# GPS.net
KiCad netlist of a schematic drawn in Altium Designer
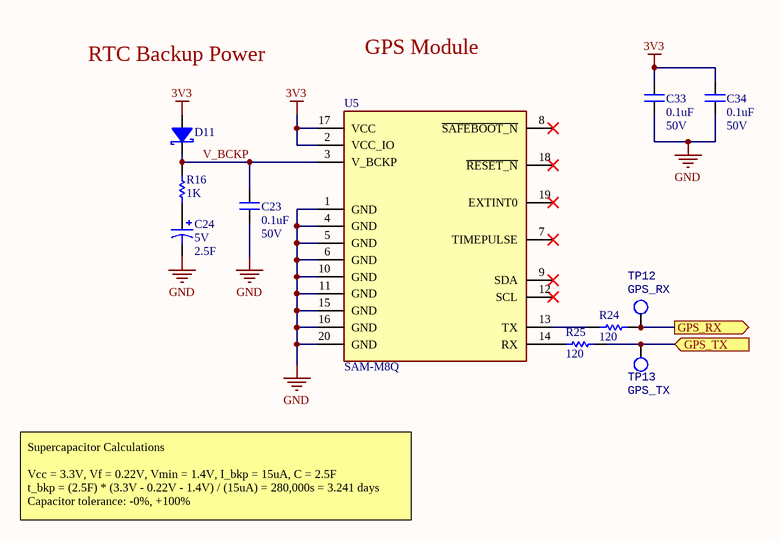
[diagram p0: GPS.SchDoc]

(export (version "E")
  (design (tool "Eeschema 10.0.6"))
  (components
    (comp (ref "C23")
      (value "0.1uF")
      (footprint "CAPC2012X140N")
      (description "CAP CER 0.1UF 50V X7R 0805")
      (fields
        (field (name "TOLERANCE") "10%")
        (field (name "VOLTAGE RATING") "50V")
        (field (name "Comment") "CAP_0.1uF_50V_0805")
      )
      (libsource (lib "UWRT_Schematic_Library_2020") (part "CAP_0.1uF_50V_0805"))
    )
    (comp (ref "C24")
      (value "CAP_2.5F_5V")
      (footprint "UWRT_Footprint_Library_2020:SCMS22C255PRBA0")
      (description "CAP 2.5F 5V")
      (fields
        (field (name "TOLERANCE") "0%, +100%")
        (field (name "VOLTAGE RATING") "5V")
        (field (name "CAPACITANCE") "2.5F")
      )
      (libsource (lib "UWRT_Schematic_Library_2020") (part "CAP_2.5F_5V"))
    )
    (comp (ref "C33")
      (value "0.1uF")
      (footprint "CAPC2012X140N")
      (description "CAP CER 0.1UF 50V X7R 0805")
      (fields
        (field (name "TOLERANCE") "10%")
        (field (name "VOLTAGE RATING") "50V")
        (field (name "Comment") "CAP_0.1uF_50V_0805")
      )
      (libsource (lib "UWRT_Schematic_Library_2020") (part "CAP_0.1uF_50V_0805"))
    )
    (comp (ref "C34")
      (value "0.1uF")
      (footprint "CAPC2012X140N")
      (description "CAP CER 0.1UF 50V X7R 0805")
      (fields
        (field (name "TOLERANCE") "10%")
        (field (name "VOLTAGE RATING") "50V")
        (field (name "Comment") "CAP_0.1uF_50V_0805")
      )
      (libsource (lib "UWRT_Schematic_Library_2020") (part "CAP_0.1uF_50V_0805"))
    )
    (comp (ref "D11")
      (value "DIO_SCHOTTKY_30V_800mA")
      (footprint "DIO_CUS520,H3F")
      (description "DIODE SCHOTTKY 30V 800MA USC")
      (libsource (lib "UWRT_Schematic_Library_2020") (part "DIO_SCHOTTKY_30V_800mA"))
    )
    (comp (ref "R16")
      (value "1K")
      (footprint "RESC0603(1608)_N")
      (description "RES SMD 1K OHM 5% 1/10W 0603")
      (fields (field (name "TOLERANCE") "5%") (field (name "Comment") "RES_1K_0603"))
      (libsource (lib "UWRT_Schematic_Library_2020") (part "RES_1K_0603"))
    )
    (comp (ref "R24")
      (value "120")
      (footprint "RESC0603(1608)_N")
      (description "RES SMD 120 OHM 5% 1/10W 0603")
      (fields (field (name "TOLERANCE") "5%") (field (name "Comment") "RES_120R_0603"))
      (libsource (lib "UWRT_Schematic_Library_2020") (part "RES_120R_0603"))
    )
    (comp (ref "R25")
      (value "120")
      (footprint "RESC0603(1608)_N")
      (description "RES SMD 120 OHM 5% 1/10W 0603")
      (fields (field (name "TOLERANCE") "5%") (field (name "Comment") "RES_120R_0603"))
      (libsource (lib "UWRT_Schematic_Library_2020") (part "RES_120R_0603"))
    )
    (comp (ref "TP12")
      (value "GPS_RX")
      (footprint "TESTPOINT_LOOP")
      (description "Loop testpoint through-hole pad")
      (libsource (lib "UWRT_Schematic_Library_2020") (part "TESTPOINT_LOOP"))
    )
    (comp (ref "TP13")
      (value "GPS_TX")
      (footprint "TESTPOINT_LOOP")
      (description "Loop testpoint through-hole pad")
      (libsource (lib "UWRT_Schematic_Library_2020") (part "TESTPOINT_LOOP"))
    )
    (comp (ref "U5")
      (value "SAM-M8Q")
      (footprint "UWRT_Footprint_Library_2020:XCVR_SAM-M8Q")
      (description "Rf Rx Galileo 1.575GHZ/1.602GHZ")
      (libsource (lib "UWRT_Schematic_Library_2020") (part "SAM-M8Q"))
    )
  )
  (nets
    (net (code "1") (name "/GPS_RX") (class "Default")
      (node (ref "R24") (pin "2") (pinfunction "2_2") (pintype "passive"))
      (node (ref "TP12") (pin "1") (pintype "passive"))
    )
    (net (code "2") (name "/GPS_TX") (class "Default")
      (node (ref "R25") (pin "2") (pinfunction "2_2") (pintype "passive"))
      (node (ref "TP13") (pin "1") (pintype "passive"))
    )
    (net (code "3") (name "/V_BCKP") (class "Default")
      (node (ref "C23") (pin "2") (pinfunction "2_2") (pintype "passive"))
      (node (ref "D11") (pin "2") (pinfunction "Cathode_2") (pintype "passive"))
      (node (ref "R16") (pin "1") (pinfunction "1_1") (pintype "passive"))
      (node (ref "U5") (pin "3") (pinfunction "V_BCKP_3") (pintype "power_in"))
    )
    (net (code "4") (name "3V3") (class "Default")
      (node (ref "C33") (pin "2") (pinfunction "2_2") (pintype "passive"))
      (node (ref "C34") (pin "2") (pinfunction "2_2") (pintype "passive"))
      (node (ref "D11") (pin "1") (pinfunction "Anode_1") (pintype "passive"))
      (node (ref "U5") (pin "17") (pinfunction "VCC_17") (pintype "power_in"))
      (node (ref "U5") (pin "2") (pinfunction "VCC_IO_2") (pintype "power_in"))
    )
    (net (code "5") (name "GND") (class "Default")
      (node (ref "C23") (pin "1") (pinfunction "1_1") (pintype "passive"))
      (node (ref "C24") (pin "2") (pinfunction "2_2") (pintype "passive"))
      (node (ref "C33") (pin "1") (pinfunction "1_1") (pintype "passive"))
      (node (ref "C34") (pin "1") (pinfunction "1_1") (pintype "passive"))
      (node (ref "U5") (pin "1") (pinfunction "GND_1") (pintype "power_in"))
      (node (ref "U5") (pin "10") (pinfunction "GND_10") (pintype "power_in"))
      (node (ref "U5") (pin "11") (pinfunction "GND_11") (pintype "power_in"))
      (node (ref "U5") (pin "15") (pinfunction "GND_15") (pintype "power_in"))
      (node (ref "U5") (pin "16") (pinfunction "GND_16") (pintype "power_in"))
      (node (ref "U5") (pin "20") (pinfunction "GND_20") (pintype "power_in"))
      (node (ref "U5") (pin "4") (pinfunction "GND_4") (pintype "power_in"))
      (node (ref "U5") (pin "5") (pinfunction "GND_5") (pintype "power_in"))
      (node (ref "U5") (pin "6") (pinfunction "GND_6") (pintype "power_in"))
    )
    (net (code "6") (name "Net-(C24-Pad1)") (class "Default")
      (node (ref "C24") (pin "1") (pinfunction "1_1") (pintype "passive"))
      (node (ref "R16") (pin "2") (pinfunction "2_2") (pintype "passive"))
    )
    (net (code "7") (name "Net-(U5-RX)") (class "Default")
      (node (ref "R25") (pin "1") (pinfunction "1_1") (pintype "passive"))
      (node (ref "U5") (pin "14") (pinfunction "RX_14") (pintype "passive"))
    )
    (net (code "8") (name "Net-(U5-TX)") (class "Default")
      (node (ref "R24") (pin "1") (pinfunction "1_1") (pintype "passive"))
      (node (ref "U5") (pin "13") (pinfunction "TX_13") (pintype "passive"))
    )
    (net (code "9") (name "unconnected-(U5-EXTINT0-Pad19)") (class "Default")
      (node (ref "U5") (pin "19") (pinfunction "EXTINT0_19") (pintype "passive+no_connect"))
    )
    (net (code "10") (name "unconnected-(U5-SCL-Pad12)") (class "Default")
      (node (ref "U5") (pin "12") (pinfunction "SCL_12") (pintype "passive+no_connect"))
    )
    (net (code "11") (name "unconnected-(U5-SDA-Pad9)") (class "Default")
      (node (ref "U5") (pin "9") (pinfunction "SDA_9") (pintype "passive+no_connect"))
    )
    (net (code "12") (name "unconnected-(U5-TIMEPULSE-Pad7)") (class "Default")
      (node (ref "U5") (pin "7") (pinfunction "TIMEPULSE_7") (pintype "passive+no_connect"))
    )
    (net (code "13") (name "unconnected-(U5-~{RESET_N}-Pad18)") (class "Default")
      (node (ref "U5") (pin "18") (pinfunction "~{RESET_N}_18") (pintype "passive+no_connect"))
    )
    (net (code "14") (name "unconnected-(U5-~{SAFEBOOT_N}-Pad8)") (class "Default")
      (node (ref "U5") (pin "8") (pinfunction "~{SAFEBOOT_N}_8") (pintype "passive+no_connect"))
    )
  )
)
